# lpc1768.net
KiCad netlist of a schematic drawn in Altium Designer
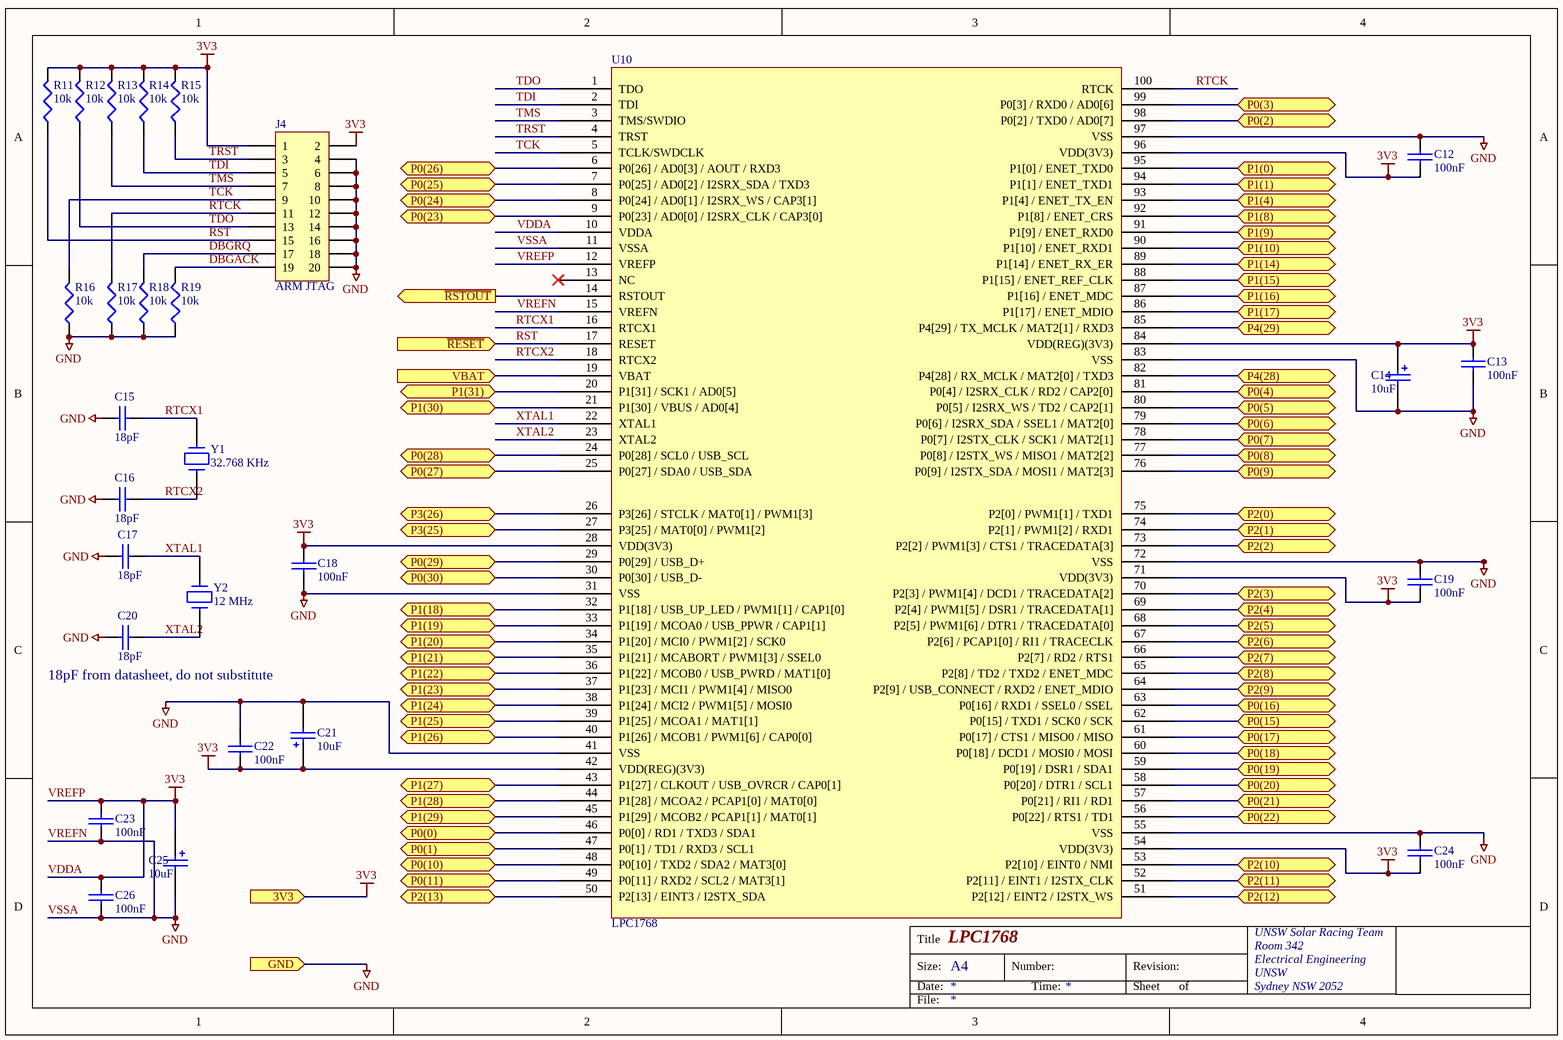
[diagram p0: lpc1768.SchDoc]

(export (version "E")
  (design (tool "Eeschema 10.0.6"))
  (components
    (comp (ref "C12")
      (value "100nF")
      (footprint "0603")
      (description "Capacitor")
      (libsource (lib "RCLDQ") (part "CAP"))
    )
    (comp (ref "C13")
      (value "100nF")
      (footprint "0603")
      (description "Capacitor")
      (libsource (lib "RCLDQ") (part "CAP"))
    )
    (comp (ref "C14")
      (value "10uF")
      (footprint "MCCT-CASEA")
      (description "Polarized Capacitor (Surface Mount)")
      (libsource (lib "RCLDQ") (part "CAP POL3"))
    )
    (comp (ref "C15")
      (value "18pF")
      (footprint "0603")
      (description "Capacitor")
      (libsource (lib "*") (part "CAP"))
    )
    (comp (ref "C16")
      (value "18pF")
      (footprint "0603")
      (description "Capacitor")
      (libsource (lib "*") (part "CAP"))
    )
    (comp (ref "C17")
      (value "18pF")
      (footprint "0603")
      (description "Capacitor")
      (libsource (lib "*") (part "CAP"))
    )
    (comp (ref "C18")
      (value "100nF")
      (footprint "0603")
      (description "Capacitor")
      (libsource (lib "RCLDQ") (part "CAP"))
    )
    (comp (ref "C19")
      (value "100nF")
      (footprint "0603")
      (description "Capacitor")
      (libsource (lib "RCLDQ") (part "CAP"))
    )
    (comp (ref "C20")
      (value "18pF")
      (footprint "0603")
      (description "Capacitor")
      (libsource (lib "*") (part "CAP"))
    )
    (comp (ref "C21")
      (value "10uF")
      (footprint "MCCT-CASEA")
      (description "Polarized Capacitor (Surface Mount)")
      (libsource (lib "RCLDQ") (part "CAP POL3"))
    )
    (comp (ref "C22")
      (value "100nF")
      (footprint "0603")
      (description "Capacitor")
      (libsource (lib "RCLDQ") (part "CAP"))
    )
    (comp (ref "C23")
      (value "100nF")
      (footprint "0603")
      (description "Capacitor")
      (libsource (lib "RCLDQ") (part "CAP"))
    )
    (comp (ref "C24")
      (value "100nF")
      (footprint "0603")
      (description "Capacitor")
      (libsource (lib "RCLDQ") (part "CAP"))
    )
    (comp (ref "C25")
      (value "10uF")
      (footprint "MCCT-CASEA")
      (description "Polarized Capacitor (Surface Mount)")
      (libsource (lib "RCLDQ") (part "CAP POL3"))
    )
    (comp (ref "C26")
      (value "100nF")
      (footprint "0603")
      (description "Capacitor")
      (libsource (lib "RCLDQ") (part "CAP"))
    )
    (comp (ref "J4")
      (value "ARM JTAG")
      (footprint "HDR2X10")
      (description "Header, 10-Pin, Dual row")
      (libsource (lib "Miscellaneous Connectors") (part "Header 10X2"))
    )
    (comp (ref "R11")
      (value "10k")
      (footprint "0603")
      (description "Resistor")
      (libsource (lib "RCLDQ") (part "RES1"))
    )
    (comp (ref "R12")
      (value "10k")
      (footprint "0603")
      (description "Resistor")
      (libsource (lib "RCLDQ") (part "RES1"))
    )
    (comp (ref "R13")
      (value "10k")
      (footprint "0603")
      (description "Resistor")
      (libsource (lib "RCLDQ") (part "RES1"))
    )
    (comp (ref "R14")
      (value "10k")
      (footprint "0603")
      (description "Resistor")
      (libsource (lib "RCLDQ") (part "RES1"))
    )
    (comp (ref "R15")
      (value "10k")
      (footprint "0603")
      (description "Resistor")
      (libsource (lib "RCLDQ") (part "RES1"))
    )
    (comp (ref "R16")
      (value "10k")
      (footprint "0603")
      (description "Resistor")
      (libsource (lib "RCLDQ") (part "RES1"))
    )
    (comp (ref "R17")
      (value "10k")
      (footprint "0603")
      (description "Resistor")
      (libsource (lib "RCLDQ") (part "RES1"))
    )
    (comp (ref "R18")
      (value "10k")
      (footprint "0603")
      (description "Resistor")
      (libsource (lib "RCLDQ") (part "RES1"))
    )
    (comp (ref "R19")
      (value "10k")
      (footprint "0603")
      (description "Resistor")
      (libsource (lib "RCLDQ") (part "RES1"))
    )
    (comp (ref "U10")
      (value "LPC1768")
      (footprint "QFP100")
      (description "NXP Cortex-M3 Microcontroller, 100pin 100MHz")
      (libsource (lib "sion") (part "LPC1768"))
    )
    (comp (ref "Y1")
      (value "32.768 KHz")
      (footprint "WATCHA")
      (description "Crystal")
      (libsource (lib "*") (part "CRYSTAL"))
    )
    (comp (ref "Y2")
      (value "12 MHz")
      (footprint "HC49/4H")
      (description "Crystal")
      (libsource (lib "*") (part "CRYSTAL"))
    )
  )
  (nets
    (net (code "1") (name "/DBGACK") (class "Default")
      (node (ref "J4") (pin "19") (pinfunction "19_19") (pintype "passive"))
      (node (ref "R19") (pin "2") (pinfunction "2_2") (pintype "passive"))
    )
    (net (code "2") (name "/DBGRQ") (class "Default")
      (node (ref "J4") (pin "17") (pinfunction "17_17") (pintype "passive"))
      (node (ref "R18") (pin "2") (pinfunction "2_2") (pintype "passive"))
    )
    (net (code "3") (name "/P0(0)") (class "Default")
      (node (ref "U10") (pin "46") (pinfunction "P0[0]_/_RD1_/_TXD3_/_SDA1_46") (pintype "passive"))
    )
    (net (code "4") (name "/P0(1)") (class "Default")
      (node (ref "U10") (pin "47") (pinfunction "P0[1]_/_TD1_/_RXD3_/_SCL1_47") (pintype "passive"))
    )
    (net (code "5") (name "/P0(2)") (class "Default")
      (node (ref "U10") (pin "98") (pinfunction "P0[2]_/_TXD0_/_AD0[7]_98") (pintype "passive"))
    )
    (net (code "6") (name "/P0(3)") (class "Default")
      (node (ref "U10") (pin "99") (pinfunction "P0[3]_/_RXD0_/_AD0[6]_99") (pintype "passive"))
    )
    (net (code "7") (name "/P0(4)") (class "Default")
      (node (ref "U10") (pin "81") (pinfunction "P0[4]_/_I2SRX_CLK_/_RD2_/_CAP2[0]_81") (pintype "passive"))
    )
    (net (code "8") (name "/P0(5)") (class "Default")
      (node (ref "U10") (pin "80") (pinfunction "P0[5]_/_I2SRX_WS_/_TD2_/_CAP2[1]_80") (pintype "passive"))
    )
    (net (code "9") (name "/P0(6)") (class "Default")
      (node (ref "U10") (pin "79") (pinfunction "P0[6]_/_I2SRX_SDA_/_SSEL1_/_MAT2[0]_79") (pintype "passive"))
    )
    (net (code "10") (name "/P0(7)") (class "Default")
      (node (ref "U10") (pin "78") (pinfunction "P0[7]_/_I2STX_CLK_/_SCK1_/_MAT2[1]_78") (pintype "passive"))
    )
    (net (code "11") (name "/P0(8)") (class "Default")
      (node (ref "U10") (pin "77") (pinfunction "P0[8]_/_I2STX_WS_/_MISO1_/_MAT2[2]_77") (pintype "passive"))
    )
    (net (code "12") (name "/P0(9)") (class "Default")
      (node (ref "U10") (pin "76") (pinfunction "P0[9]_/_I2STX_SDA_/_MOSI1_/_MAT2[3]_76") (pintype "passive"))
    )
    (net (code "13") (name "/P0(10)") (class "Default")
      (node (ref "U10") (pin "48") (pinfunction "P0[10]_/_TXD2_/_SDA2_/_MAT3[0]_48") (pintype "passive"))
    )
    (net (code "14") (name "/P0(11)") (class "Default")
      (node (ref "U10") (pin "49") (pinfunction "P0[11]_/_RXD2_/_SCL2_/_MAT3[1]_49") (pintype "passive"))
    )
    (net (code "15") (name "/P0(15)") (class "Default")
      (node (ref "U10") (pin "62") (pinfunction "P0[15]_/_TXD1_/_SCK0_/_SCK_62") (pintype "passive"))
    )
    (net (code "16") (name "/P0(16)") (class "Default")
      (node (ref "U10") (pin "63") (pinfunction "P0[16]_/_RXD1_/_SSEL0_/_SSEL_63") (pintype "passive"))
    )
    (net (code "17") (name "/P0(17)") (class "Default")
      (node (ref "U10") (pin "61") (pinfunction "P0[17]_/_CTS1_/_MISO0_/_MISO_61") (pintype "passive"))
    )
    (net (code "18") (name "/P0(18)") (class "Default")
      (node (ref "U10") (pin "60") (pinfunction "P0[18]_/_DCD1_/_MOSI0_/_MOSI_60") (pintype "passive"))
    )
    (net (code "19") (name "/P0(19)") (class "Default")
      (node (ref "U10") (pin "59") (pinfunction "P0[19]_/_DSR1_/_SDA1_59") (pintype "passive"))
    )
    (net (code "20") (name "/P0(20)") (class "Default")
      (node (ref "U10") (pin "58") (pinfunction "P0[20]_/_DTR1_/_SCL1_58") (pintype "passive"))
    )
    (net (code "21") (name "/P0(21)") (class "Default")
      (node (ref "U10") (pin "57") (pinfunction "P0[21]_/_RI1_/_RD1_57") (pintype "passive"))
    )
    (net (code "22") (name "/P0(22)") (class "Default")
      (node (ref "U10") (pin "56") (pinfunction "P0[22]_/_RTS1_/_TD1_56") (pintype "passive"))
    )
    (net (code "23") (name "/P0(23)") (class "Default")
      (node (ref "U10") (pin "9") (pinfunction "P0[23]_/_AD0[0]_/_I2SRX_CLK_/_CAP3[0]_9") (pintype "passive"))
    )
    (net (code "24") (name "/P0(24)") (class "Default")
      (node (ref "U10") (pin "8") (pinfunction "P0[24]_/_AD0[1]_/_I2SRX_WS_/_CAP3[1]_8") (pintype "passive"))
    )
    (net (code "25") (name "/P0(25)") (class "Default")
      (node (ref "U10") (pin "7") (pinfunction "P0[25]_/_AD0[2]_/_I2SRX_SDA_/_TXD3_7") (pintype "passive"))
    )
    (net (code "26") (name "/P0(26)") (class "Default")
      (node (ref "U10") (pin "6") (pinfunction "P0[26]_/_AD0[3]_/_AOUT_/_RXD3_6") (pintype "passive"))
    )
    (net (code "27") (name "/P0(27)") (class "Default")
      (node (ref "U10") (pin "25") (pinfunction "P0[27]_/_SDA0_/_USB_SDA_25") (pintype "passive"))
    )
    (net (code "28") (name "/P0(28)") (class "Default")
      (node (ref "U10") (pin "24") (pinfunction "P0[28]_/_SCL0_/_USB_SCL_24") (pintype "passive"))
    )
    (net (code "29") (name "/P0(29)") (class "Default")
      (node (ref "U10") (pin "29") (pinfunction "P0[29]_/_USB_D+_29") (pintype "passive"))
    )
    (net (code "30") (name "/P0(30)") (class "Default")
      (node (ref "U10") (pin "30") (pinfunction "P0[30]_/_USB_D-_30") (pintype "passive"))
    )
    (net (code "31") (name "/P1(0)") (class "Default")
      (node (ref "U10") (pin "95") (pinfunction "P1[0]_/_ENET_TXD0_95") (pintype "passive"))
    )
    (net (code "32") (name "/P1(1)") (class "Default")
      (node (ref "U10") (pin "94") (pinfunction "P1[1]_/_ENET_TXD1_94") (pintype "passive"))
    )
    (net (code "33") (name "/P1(4)") (class "Default")
      (node (ref "U10") (pin "93") (pinfunction "P1[4]_/_ENET_TX_EN_93") (pintype "passive"))
    )
    (net (code "34") (name "/P1(8)") (class "Default")
      (node (ref "U10") (pin "92") (pinfunction "P1[8]_/_ENET_CRS_92") (pintype "passive"))
    )
    (net (code "35") (name "/P1(9)") (class "Default")
      (node (ref "U10") (pin "91") (pinfunction "P1[9]_/_ENET_RXD0_91") (pintype "passive"))
    )
    (net (code "36") (name "/P1(10)") (class "Default")
      (node (ref "U10") (pin "90") (pinfunction "P1[10]_/_ENET_RXD1_90") (pintype "passive"))
    )
    (net (code "37") (name "/P1(14)") (class "Default")
      (node (ref "U10") (pin "89") (pinfunction "P1[14]_/_ENET_RX_ER_89") (pintype "passive"))
    )
    (net (code "38") (name "/P1(15)") (class "Default")
      (node (ref "U10") (pin "88") (pinfunction "P1[15]_/_ENET_REF_CLK_88") (pintype "passive"))
    )
    (net (code "39") (name "/P1(16)") (class "Default")
      (node (ref "U10") (pin "87") (pinfunction "P1[16]_/_ENET_MDC_87") (pintype "passive"))
    )
    (net (code "40") (name "/P1(17)") (class "Default")
      (node (ref "U10") (pin "86") (pinfunction "P1[17]_/_ENET_MDIO_86") (pintype "passive"))
    )
    (net (code "41") (name "/P1(18)") (class "Default")
      (node (ref "U10") (pin "32") (pinfunction "P1[18]_/_USB_UP_LED_/_PWM1[1]_/_CAP1[0]_32") (pintype "passive"))
    )
    (net (code "42") (name "/P1(19)") (class "Default")
      (node (ref "U10") (pin "33") (pinfunction "P1[19]_/_MCOA0_/_USB_PPWR_/_CAP1[1]_33") (pintype "passive"))
    )
    (net (code "43") (name "/P1(20)") (class "Default")
      (node (ref "U10") (pin "34") (pinfunction "P1[20]_/_MCI0_/_PWM1[2]_/_SCK0_34") (pintype "passive"))
    )
    (net (code "44") (name "/P1(21)") (class "Default")
      (node (ref "U10") (pin "35") (pinfunction "P1[21]_/_MCABORT_/_PWM1[3]_/_SSEL0_35") (pintype "passive"))
    )
    (net (code "45") (name "/P1(22)") (class "Default")
      (node (ref "U10") (pin "36") (pinfunction "P1[22]_/_MCOB0_/_USB_PWRD_/_MAT1[0]_36") (pintype "passive"))
    )
    (net (code "46") (name "/P1(23)") (class "Default")
      (node (ref "U10") (pin "37") (pinfunction "P1[23]_/_MCI1_/_PWM1[4]_/_MISO0_37") (pintype "passive"))
    )
    (net (code "47") (name "/P1(24)") (class "Default")
      (node (ref "U10") (pin "38") (pinfunction "P1[24]_/_MCI2_/_PWM1[5]_/_MOSI0_38") (pintype "passive"))
    )
    (net (code "48") (name "/P1(25)") (class "Default")
      (node (ref "U10") (pin "39") (pinfunction "P1[25]_/_MCOA1_/_MAT1[1]_39") (pintype "passive"))
    )
    (net (code "49") (name "/P1(26)") (class "Default")
      (node (ref "U10") (pin "40") (pinfunction "P1[26]_/_MCOB1_/_PWM1[6]_/_CAP0[0]_40") (pintype "passive"))
    )
    (net (code "50") (name "/P1(27)") (class "Default")
      (node (ref "U10") (pin "43") (pinfunction "P1[27]_/_CLKOUT_/_USB_OVRCR_/_CAP0[1]_43") (pintype "passive"))
    )
    (net (code "51") (name "/P1(28)") (class "Default")
      (node (ref "U10") (pin "44") (pinfunction "P1[28]_/_MCOA2_/_PCAP1[0]_/_MAT0[0]_44") (pintype "passive"))
    )
    (net (code "52") (name "/P1(29)") (class "Default")
      (node (ref "U10") (pin "45") (pinfunction "P1[29]_/_MCOB2_/_PCAP1[1]_/_MAT0[1]_45") (pintype "passive"))
    )
    (net (code "53") (name "/P1(30)") (class "Default")
      (node (ref "U10") (pin "21") (pinfunction "P1[30]_/_VBUS_/_AD0[4]_21") (pintype "passive"))
    )
    (net (code "54") (name "/P1(31)") (class "Default")
      (node (ref "U10") (pin "20") (pinfunction "P1[31]_/_SCK1_/_AD0[5]_20") (pintype "passive"))
    )
    (net (code "55") (name "/P2(0)") (class "Default")
      (node (ref "U10") (pin "75") (pinfunction "P2[0]_/_PWM1[1]_/_TXD1_75") (pintype "passive"))
    )
    (net (code "56") (name "/P2(1)") (class "Default")
      (node (ref "U10") (pin "74") (pinfunction "P2[1]_/_PWM1[2]_/_RXD1_74") (pintype "passive"))
    )
    (net (code "57") (name "/P2(2)") (class "Default")
      (node (ref "U10") (pin "73") (pinfunction "P2[2]_/_PWM1[3]_/_CTS1_/_TRACEDATA[3]_73") (pintype "passive"))
    )
    (net (code "58") (name "/P2(3)") (class "Default")
      (node (ref "U10") (pin "70") (pinfunction "P2[3]_/_PWM1[4]_/_DCD1_/_TRACEDATA[2]_70") (pintype "passive"))
    )
    (net (code "59") (name "/P2(4)") (class "Default")
      (node (ref "U10") (pin "69") (pinfunction "P2[4]_/_PWM1[5]_/_DSR1_/_TRACEDATA[1]_69") (pintype "passive"))
    )
    (net (code "60") (name "/P2(5)") (class "Default")
      (node (ref "U10") (pin "68") (pinfunction "P2[5]_/_PWM1[6]_/_DTR1_/_TRACEDATA[0]_68") (pintype "passive"))
    )
    (net (code "61") (name "/P2(6)") (class "Default")
      (node (ref "U10") (pin "67") (pinfunction "P2[6]_/_PCAP1[0]_/_RI1_/_TRACECLK_67") (pintype "passive"))
    )
    (net (code "62") (name "/P2(7)") (class "Default")
      (node (ref "U10") (pin "66") (pinfunction "P2[7]_/_RD2_/_RTS1_66") (pintype "passive"))
    )
    (net (code "63") (name "/P2(8)") (class "Default")
      (node (ref "U10") (pin "65") (pinfunction "P2[8]_/_TD2_/_TXD2_/_ENET_MDC_65") (pintype "passive"))
    )
    (net (code "64") (name "/P2(9)") (class "Default")
      (node (ref "U10") (pin "64") (pinfunction "P2[9]_/_USB_CONNECT_/_RXD2_/_ENET_MDIO_64") (pintype "passive"))
    )
    (net (code "65") (name "/P2(10)") (class "Default")
      (node (ref "U10") (pin "53") (pinfunction "P2[10]_/_EINT0_/_NMI_53") (pintype "passive"))
    )
    (net (code "66") (name "/P2(11)") (class "Default")
      (node (ref "U10") (pin "52") (pinfunction "P2[11]_/_EINT1_/_I2STX_CLK_52") (pintype "passive"))
    )
    (net (code "67") (name "/P2(12)") (class "Default")
      (node (ref "U10") (pin "51") (pinfunction "P2[12]_/_EINT2_/_I2STX_WS_51") (pintype "passive"))
    )
    (net (code "68") (name "/P2(13)") (class "Default")
      (node (ref "U10") (pin "50") (pinfunction "P2[13]_/_EINT3_/_I2STX_SDA_50") (pintype "passive"))
    )
    (net (code "69") (name "/P3(25)") (class "Default")
      (node (ref "U10") (pin "27") (pinfunction "P3[25]_/_MAT0[0]_/_PWM1[2]_27") (pintype "passive"))
    )
    (net (code "70") (name "/P3(26)") (class "Default")
      (node (ref "U10") (pin "26") (pinfunction "P3[26]_/_STCLK_/_MAT0[1]_/_PWM1[3]_26") (pintype "passive"))
    )
    (net (code "71") (name "/P4(28)") (class "Default")
      (node (ref "U10") (pin "82") (pinfunction "P4[28]_/_RX_MCLK_/_MAT2[0]_/_TXD3_82") (pintype "passive"))
    )
    (net (code "72") (name "/P4(29)") (class "Default")
      (node (ref "U10") (pin "85") (pinfunction "P4[29]_/_TX_MCLK_/_MAT2[1]_/_RXD3_85") (pintype "passive"))
    )
    (net (code "73") (name "/RST") (class "Default")
      (node (ref "J4") (pin "15") (pinfunction "15_15") (pintype "passive"))
      (node (ref "R11") (pin "1") (pinfunction "1_1") (pintype "passive"))
      (node (ref "U10") (pin "17") (pinfunction "RESET_17") (pintype "passive"))
    )
    (net (code "74") (name "/RTCK") (class "Default")
      (node (ref "J4") (pin "11") (pinfunction "11_11") (pintype "passive"))
      (node (ref "R17") (pin "2") (pinfunction "2_2") (pintype "passive"))
      (node (ref "U10") (pin "100") (pinfunction "RTCK_100") (pintype "passive"))
    )
    (net (code "75") (name "/RTCX1") (class "Default")
      (node (ref "C15") (pin "1") (pinfunction "1_1") (pintype "passive"))
      (node (ref "U10") (pin "16") (pinfunction "RTCX1_16") (pintype "passive"))
      (node (ref "Y1") (pin "2") (pinfunction "2_2") (pintype "passive"))
    )
    (net (code "76") (name "/RTCX2") (class "Default")
      (node (ref "C16") (pin "1") (pinfunction "1_1") (pintype "passive"))
      (node (ref "U10") (pin "18") (pinfunction "RTCX2_18") (pintype "passive"))
      (node (ref "Y1") (pin "1") (pinfunction "1_1") (pintype "passive"))
    )
    (net (code "77") (name "/TCK") (class "Default")
      (node (ref "J4") (pin "9") (pinfunction "9_9") (pintype "passive"))
      (node (ref "R16") (pin "2") (pinfunction "2_2") (pintype "passive"))
      (node (ref "U10") (pin "5") (pinfunction "TCLK/SWDCLK_5") (pintype "passive"))
    )
    (net (code "78") (name "/TDI") (class "Default")
      (node (ref "J4") (pin "5") (pinfunction "5_5") (pintype "passive"))
      (node (ref "R14") (pin "1") (pinfunction "1_1") (pintype "passive"))
      (node (ref "U10") (pin "2") (pinfunction "TDI_2") (pintype "passive"))
    )
    (net (code "79") (name "/TDO") (class "Default")
      (node (ref "J4") (pin "13") (pinfunction "13_13") (pintype "passive"))
      (node (ref "R12") (pin "1") (pinfunction "1_1") (pintype "passive"))
      (node (ref "U10") (pin "1") (pinfunction "TDO_1") (pintype "passive"))
    )
    (net (code "80") (name "/TMS") (class "Default")
      (node (ref "J4") (pin "7") (pinfunction "7_7") (pintype "passive"))
      (node (ref "R13") (pin "1") (pinfunction "1_1") (pintype "passive"))
      (node (ref "U10") (pin "3") (pinfunction "TMS/SWDIO_3") (pintype "passive"))
    )
    (net (code "81") (name "/TRST") (class "Default")
      (node (ref "J4") (pin "3") (pinfunction "3_3") (pintype "passive"))
      (node (ref "R15") (pin "1") (pinfunction "1_1") (pintype "passive"))
      (node (ref "U10") (pin "4") (pinfunction "TRST_4") (pintype "passive"))
    )
    (net (code "82") (name "/VBAT") (class "Default")
      (node (ref "U10") (pin "19") (pinfunction "VBAT_19") (pintype "passive"))
    )
    (net (code "83") (name "/XTAL1") (class "Default")
      (node (ref "C17") (pin "1") (pinfunction "1_1") (pintype "passive"))
      (node (ref "U10") (pin "22") (pinfunction "XTAL1_22") (pintype "passive"))
      (node (ref "Y2") (pin "1") (pinfunction "1_1") (pintype "passive"))
    )
    (net (code "84") (name "/XTAL2") (class "Default")
      (node (ref "C20") (pin "1") (pinfunction "1_1") (pintype "passive"))
      (node (ref "U10") (pin "23") (pinfunction "XTAL2_23") (pintype "passive"))
      (node (ref "Y2") (pin "2") (pinfunction "2_2") (pintype "passive"))
    )
    (net (code "85") (name "/~{RSTOUT}") (class "Default")
      (node (ref "U10") (pin "14") (pinfunction "RSTOUT_14") (pintype "passive"))
    )
    (net (code "86") (name "3V3") (class "Default")
      (node (ref "C12") (pin "2") (pinfunction "2_2") (pintype "passive"))
      (node (ref "C13") (pin "1") (pinfunction "1_1") (pintype "passive"))
      (node (ref "C14") (pin "1") (pinfunction "1_1") (pintype "passive"))
      (node (ref "C18") (pin "1") (pinfunction "1_1") (pintype "passive"))
      (node (ref "C19") (pin "2") (pinfunction "2_2") (pintype "passive"))
      (node (ref "C21") (pin "1") (pinfunction "1_1") (pintype "passive"))
      (node (ref "C22") (pin "2") (pinfunction "2_2") (pintype "passive"))
      (node (ref "C23") (pin "1") (pinfunction "1_1") (pintype "passive"))
      (node (ref "C24") (pin "2") (pinfunction "2_2") (pintype "passive"))
      (node (ref "C25") (pin "1") (pinfunction "1_1") (pintype "passive"))
      (node (ref "C26") (pin "1") (pinfunction "1_1") (pintype "passive"))
      (node (ref "J4") (pin "1") (pinfunction "1_1") (pintype "passive"))
      (node (ref "J4") (pin "2") (pinfunction "2_2") (pintype "passive"))
      (node (ref "R11") (pin "2") (pinfunction "2_2") (pintype "passive"))
      (node (ref "R12") (pin "2") (pinfunction "2_2") (pintype "passive"))
      (node (ref "R13") (pin "2") (pinfunction "2_2") (pintype "passive"))
      (node (ref "R14") (pin "2") (pinfunction "2_2") (pintype "passive"))
      (node (ref "R15") (pin "2") (pinfunction "2_2") (pintype "passive"))
      (node (ref "U10") (pin "10") (pinfunction "VDDA_10") (pintype "passive"))
      (node (ref "U10") (pin "12") (pinfunction "VREFP_12") (pintype "passive"))
      (node (ref "U10") (pin "28") (pinfunction "VDD(3V3)_28") (pintype "passive"))
      (node (ref "U10") (pin "42") (pinfunction "VDD(REG)(3V3)_42") (pintype "passive"))
      (node (ref "U10") (pin "54") (pinfunction "VDD(3V3)_54") (pintype "passive"))
      (node (ref "U10") (pin "71") (pinfunction "VDD(3V3)_71") (pintype "passive"))
      (node (ref "U10") (pin "84") (pinfunction "VDD(REG)(3V3)_84") (pintype "passive"))
      (node (ref "U10") (pin "96") (pinfunction "VDD(3V3)_96") (pintype "passive"))
    )
    (net (code "87") (name "GND") (class "Default")
      (node (ref "C12") (pin "1") (pinfunction "1_1") (pintype "passive"))
      (node (ref "C13") (pin "2") (pinfunction "2_2") (pintype "passive"))
      (node (ref "C14") (pin "2") (pinfunction "2_2") (pintype "passive"))
      (node (ref "C15") (pin "2") (pinfunction "2_2") (pintype "passive"))
      (node (ref "C16") (pin "2") (pinfunction "2_2") (pintype "passive"))
      (node (ref "C17") (pin "2") (pinfunction "2_2") (pintype "passive"))
      (node (ref "C18") (pin "2") (pinfunction "2_2") (pintype "passive"))
      (node (ref "C19") (pin "1") (pinfunction "1_1") (pintype "passive"))
      (node (ref "C20") (pin "2") (pinfunction "2_2") (pintype "passive"))
      (node (ref "C21") (pin "2") (pinfunction "2_2") (pintype "passive"))
      (node (ref "C22") (pin "1") (pinfunction "1_1") (pintype "passive"))
      (node (ref "C23") (pin "2") (pinfunction "2_2") (pintype "passive"))
      (node (ref "C24") (pin "1") (pinfunction "1_1") (pintype "passive"))
      (node (ref "C25") (pin "2") (pinfunction "2_2") (pintype "passive"))
      (node (ref "C26") (pin "2") (pinfunction "2_2") (pintype "passive"))
      (node (ref "J4") (pin "10") (pinfunction "10_10") (pintype "passive"))
      (node (ref "J4") (pin "12") (pinfunction "12_12") (pintype "passive"))
      (node (ref "J4") (pin "14") (pinfunction "14_14") (pintype "passive"))
      (node (ref "J4") (pin "16") (pinfunction "16_16") (pintype "passive"))
      (node (ref "J4") (pin "18") (pinfunction "18_18") (pintype "passive"))
      (node (ref "J4") (pin "20") (pinfunction "20_20") (pintype "passive"))
      (node (ref "J4") (pin "4") (pinfunction "4_4") (pintype "passive"))
      (node (ref "J4") (pin "6") (pinfunction "6_6") (pintype "passive"))
      (node (ref "J4") (pin "8") (pinfunction "8_8") (pintype "passive"))
      (node (ref "R16") (pin "1") (pinfunction "1_1") (pintype "passive"))
      (node (ref "R17") (pin "1") (pinfunction "1_1") (pintype "passive"))
      (node (ref "R18") (pin "1") (pinfunction "1_1") (pintype "passive"))
      (node (ref "R19") (pin "1") (pinfunction "1_1") (pintype "passive"))
      (node (ref "U10") (pin "11") (pinfunction "VSSA_11") (pintype "passive"))
      (node (ref "U10") (pin "15") (pinfunction "VREFN_15") (pintype "passive"))
      (node (ref "U10") (pin "31") (pinfunction "VSS_31") (pintype "passive"))
      (node (ref "U10") (pin "41") (pinfunction "VSS_41") (pintype "passive"))
      (node (ref "U10") (pin "55") (pinfunction "VSS_55") (pintype "passive"))
      (node (ref "U10") (pin "72") (pinfunction "VSS_72") (pintype "passive"))
      (node (ref "U10") (pin "83") (pinfunction "VSS_83") (pintype "passive"))
      (node (ref "U10") (pin "97") (pinfunction "VSS_97") (pintype "passive"))
    )
    (net (code "88") (name "unconnected-(U10-NC-Pad13)") (class "Default")
      (node (ref "U10") (pin "13") (pinfunction "NC_13") (pintype "passive+no_connect"))
    )
  )
)
